# Shield_Proto.net
KiCad netlist of a schematic drawn in EAGLE
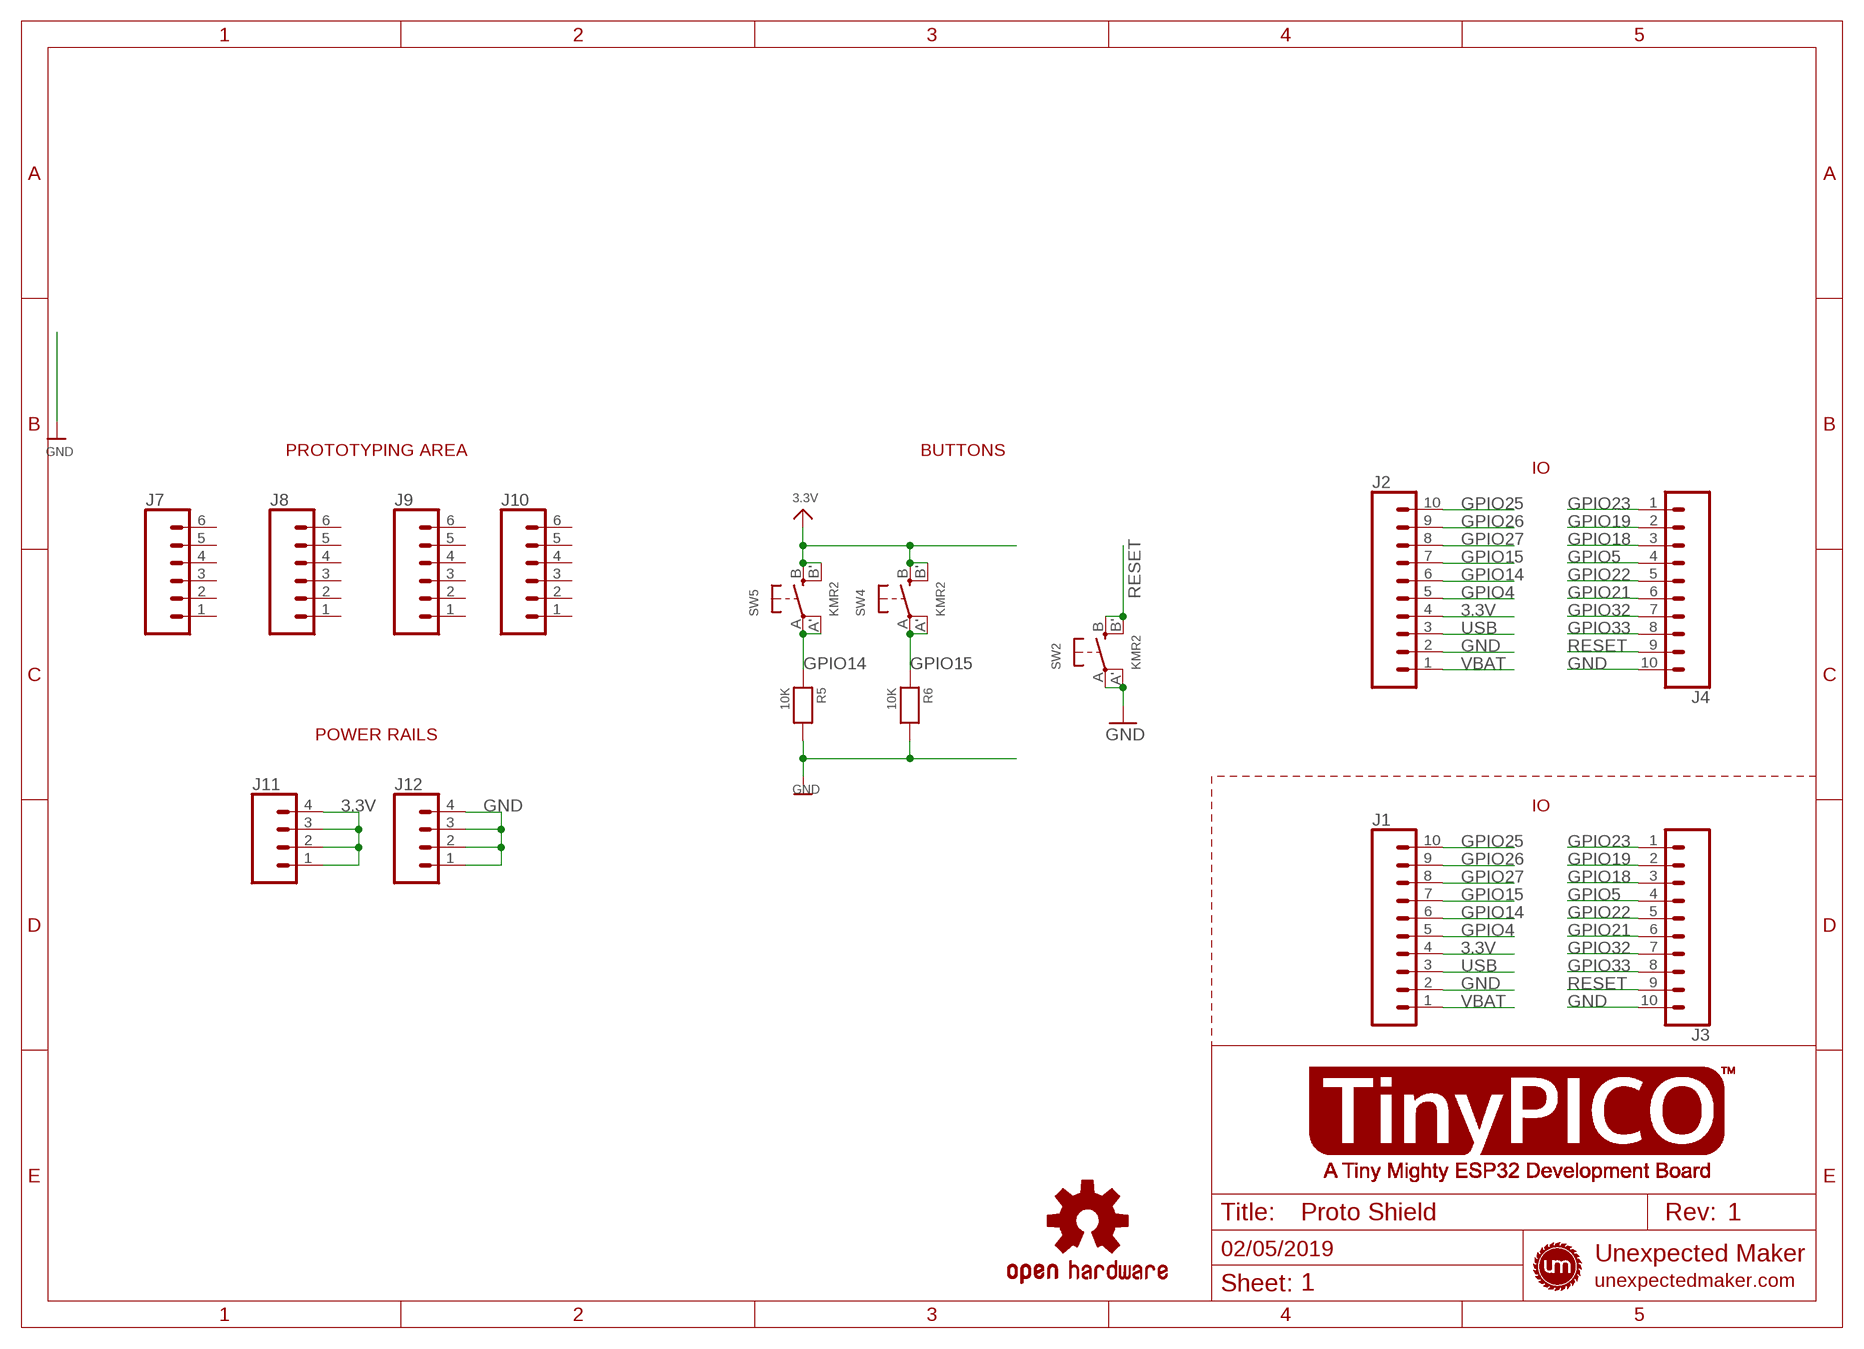
[diagram p0: schematic, sheet 1]

(export (version "E")
  (design (tool "Eeschema 10.0.6"))
  (components
    (comp (ref "J1")
      (value "TINYPICO_HEADER_10NO_SILK_PTH_FEMALE")
      (footprint "eagle-import:1X10_NO_SILK")
      (libsource (lib "eagle-import") (part "TINYPICO_HEADER_10NO_SILK_PTH_FEMALE"))
    )
    (comp (ref "J2")
      (value "TINYPICO_HEADER_10NO_SILK_PTH_FEMALE")
      (footprint "eagle-import:1X10_NO_SILK")
      (libsource (lib "eagle-import") (part "TINYPICO_HEADER_10NO_SILK_PTH_FEMALE"))
    )
    (comp (ref "J3")
      (value "TINYPICO_HEADER_10NO_SILK_PTH_FEMALE")
      (footprint "eagle-import:1X10_NO_SILK")
      (libsource (lib "eagle-import") (part "TINYPICO_HEADER_10NO_SILK_PTH_FEMALE"))
    )
    (comp (ref "J4")
      (value "TINYPICO_HEADER_10NO_SILK_PTH_FEMALE")
      (footprint "eagle-import:1X10_NO_SILK")
      (libsource (lib "eagle-import") (part "TINYPICO_HEADER_10NO_SILK_PTH_FEMALE"))
    )
    (comp (ref "J7")
      (value "CONNECTORS_CONN_06NO_SILK_NO_POP")
      (footprint "eagle-import:SPARKFUN-CONNECTORS_1X06_NO_SILK")
      (libsource (lib "eagle-import") (part "CONNECTORS_CONN_06NO_SILK_NO_POP"))
    )
    (comp (ref "J8")
      (value "CONNECTORS_CONN_06NO_SILK_NO_POP")
      (footprint "eagle-import:SPARKFUN-CONNECTORS_1X06_NO_SILK")
      (libsource (lib "eagle-import") (part "CONNECTORS_CONN_06NO_SILK_NO_POP"))
    )
    (comp (ref "J9")
      (value "CONNECTORS_CONN_06NO_SILK_NO_POP")
      (footprint "eagle-import:SPARKFUN-CONNECTORS_1X06_NO_SILK")
      (libsource (lib "eagle-import") (part "CONNECTORS_CONN_06NO_SILK_NO_POP"))
    )
    (comp (ref "J10")
      (value "CONNECTORS_CONN_06NO_SILK_NO_POP")
      (footprint "eagle-import:SPARKFUN-CONNECTORS_1X06_NO_SILK")
      (libsource (lib "eagle-import") (part "CONNECTORS_CONN_06NO_SILK_NO_POP"))
    )
    (comp (ref "J11")
      (value "CONN_041X04_NO_SILK")
      (footprint "eagle-import:1X04_NO_SILK")
      (libsource (lib "eagle-import") (part "CONN_041X04_NO_SILK"))
    )
    (comp (ref "J12")
      (value "CONN_041X04_NO_SILK")
      (footprint "eagle-import:1X04_NO_SILK")
      (libsource (lib "eagle-import") (part "CONN_041X04_NO_SILK"))
    )
    (comp (ref "LOGO1")
      (value "OSHW-LOGOS")
      (footprint "eagle-import:OSHW-LOGO-S")
      (libsource (lib "eagle-import") (part "OSHW-LOGOS"))
    )
    (comp (ref "R5")
      (value "10K")
      (footprint "eagle-import:_0603MP")
      (libsource (lib "eagle-import") (part "RESISTOR_0603MP"))
    )
    (comp (ref "R6")
      (value "10K")
      (footprint "eagle-import:_0603MP")
      (libsource (lib "eagle-import") (part "RESISTOR_0603MP"))
    )
    (comp (ref "SW2")
      (value "KMR2")
      (footprint "eagle-import:BTN_KMR2_4.6X2.8")
      (libsource (lib "eagle-import") (part "SWITCH_TACT_SMT4.6X2.8"))
    )
    (comp (ref "SW4")
      (value "KMR2")
      (footprint "eagle-import:BTN_KMR2_4.6X2.8")
      (libsource (lib "eagle-import") (part "SWITCH_TACT_SMT4.6X2.8"))
    )
    (comp (ref "SW5")
      (value "KMR2")
      (footprint "eagle-import:BTN_KMR2_4.6X2.8")
      (libsource (lib "eagle-import") (part "SWITCH_TACT_SMT4.6X2.8"))
    )
  )
  (nets
    (net (code "1") (name "/GPIO4") (class "Default")
      (node (ref "J1") (pin "5") (pinfunction "5_5") (pintype "passive"))
      (node (ref "J2") (pin "5") (pinfunction "5_5") (pintype "passive"))
    )
    (net (code "2") (name "/GPIO5") (class "Default")
      (node (ref "J3") (pin "4") (pinfunction "4_4") (pintype "passive"))
      (node (ref "J4") (pin "4") (pinfunction "4_4") (pintype "passive"))
    )
    (net (code "3") (name "/GPIO14") (class "Default")
      (node (ref "J1") (pin "6") (pinfunction "6_6") (pintype "passive"))
      (node (ref "J2") (pin "6") (pinfunction "6_6") (pintype "passive"))
      (node (ref "R5") (pin "1") (pinfunction "1_1") (pintype "passive"))
      (node (ref "SW5") (pin "A") (pinfunction "P_A") (pintype "passive"))
      (node (ref "SW5") (pin "A'") (pinfunction "P1_A'") (pintype "passive"))
    )
    (net (code "4") (name "/GPIO15") (class "Default")
      (node (ref "J1") (pin "7") (pinfunction "7_7") (pintype "passive"))
      (node (ref "J2") (pin "7") (pinfunction "7_7") (pintype "passive"))
      (node (ref "R6") (pin "1") (pinfunction "1_1") (pintype "passive"))
      (node (ref "SW4") (pin "A") (pinfunction "P_A") (pintype "passive"))
      (node (ref "SW4") (pin "A'") (pinfunction "P1_A'") (pintype "passive"))
    )
    (net (code "5") (name "/GPIO18") (class "Default")
      (node (ref "J3") (pin "3") (pinfunction "3_3") (pintype "passive"))
      (node (ref "J4") (pin "3") (pinfunction "3_3") (pintype "passive"))
    )
    (net (code "6") (name "/GPIO19") (class "Default")
      (node (ref "J3") (pin "2") (pinfunction "2_2") (pintype "passive"))
      (node (ref "J4") (pin "2") (pinfunction "2_2") (pintype "passive"))
    )
    (net (code "7") (name "/GPIO21") (class "Default")
      (node (ref "J3") (pin "6") (pinfunction "6_6") (pintype "passive"))
      (node (ref "J4") (pin "6") (pinfunction "6_6") (pintype "passive"))
    )
    (net (code "8") (name "/GPIO22") (class "Default")
      (node (ref "J3") (pin "5") (pinfunction "5_5") (pintype "passive"))
      (node (ref "J4") (pin "5") (pinfunction "5_5") (pintype "passive"))
    )
    (net (code "9") (name "/GPIO23") (class "Default")
      (node (ref "J3") (pin "1") (pinfunction "1_1") (pintype "passive"))
      (node (ref "J4") (pin "1") (pinfunction "1_1") (pintype "passive"))
    )
    (net (code "10") (name "/GPIO25") (class "Default")
      (node (ref "J1") (pin "10") (pinfunction "10_10") (pintype "passive"))
      (node (ref "J2") (pin "10") (pinfunction "10_10") (pintype "passive"))
    )
    (net (code "11") (name "/GPIO26") (class "Default")
      (node (ref "J1") (pin "9") (pinfunction "9_9") (pintype "passive"))
      (node (ref "J2") (pin "9") (pinfunction "9_9") (pintype "passive"))
    )
    (net (code "12") (name "/GPIO27") (class "Default")
      (node (ref "J1") (pin "8") (pinfunction "8_8") (pintype "passive"))
      (node (ref "J2") (pin "8") (pinfunction "8_8") (pintype "passive"))
    )
    (net (code "13") (name "/GPIO32") (class "Default")
      (node (ref "J3") (pin "7") (pinfunction "7_7") (pintype "passive"))
      (node (ref "J4") (pin "7") (pinfunction "7_7") (pintype "passive"))
    )
    (net (code "14") (name "/GPIO33") (class "Default")
      (node (ref "J3") (pin "8") (pinfunction "8_8") (pintype "passive"))
      (node (ref "J4") (pin "8") (pinfunction "8_8") (pintype "passive"))
    )
    (net (code "15") (name "/RESET") (class "Default")
      (node (ref "J3") (pin "9") (pinfunction "9_9") (pintype "passive"))
      (node (ref "J4") (pin "9") (pinfunction "9_9") (pintype "passive"))
      (node (ref "SW2") (pin "B") (pinfunction "S_B") (pintype "passive"))
      (node (ref "SW2") (pin "B'") (pinfunction "S1_B'") (pintype "passive"))
    )
    (net (code "16") (name "/USB") (class "Default")
      (node (ref "J1") (pin "3") (pinfunction "3_3") (pintype "passive"))
      (node (ref "J2") (pin "3") (pinfunction "3_3") (pintype "passive"))
    )
    (net (code "17") (name "/VBAT") (class "Default")
      (node (ref "J1") (pin "1") (pinfunction "1_1") (pintype "passive"))
      (node (ref "J2") (pin "1") (pinfunction "1_1") (pintype "passive"))
    )
    (net (code "18") (name "3.3V") (class "Default")
      (node (ref "J1") (pin "4") (pinfunction "4_4") (pintype "passive"))
      (node (ref "J11") (pin "1") (pinfunction "1_1") (pintype "passive"))
      (node (ref "J11") (pin "2") (pinfunction "2_2") (pintype "passive"))
      (node (ref "J11") (pin "3") (pinfunction "3_3") (pintype "passive"))
      (node (ref "J11") (pin "4") (pinfunction "4_4") (pintype "passive"))
      (node (ref "J2") (pin "4") (pinfunction "4_4") (pintype "passive"))
      (node (ref "SW4") (pin "B") (pinfunction "S_B") (pintype "passive"))
      (node (ref "SW4") (pin "B'") (pinfunction "S1_B'") (pintype "passive"))
      (node (ref "SW5") (pin "B") (pinfunction "S_B") (pintype "passive"))
      (node (ref "SW5") (pin "B'") (pinfunction "S1_B'") (pintype "passive"))
    )
    (net (code "19") (name "GND") (class "Default")
      (node (ref "J1") (pin "2") (pinfunction "2_2") (pintype "passive"))
      (node (ref "J12") (pin "1") (pinfunction "1_1") (pintype "passive"))
      (node (ref "J12") (pin "2") (pinfunction "2_2") (pintype "passive"))
      (node (ref "J12") (pin "3") (pinfunction "3_3") (pintype "passive"))
      (node (ref "J12") (pin "4") (pinfunction "4_4") (pintype "passive"))
      (node (ref "J2") (pin "2") (pinfunction "2_2") (pintype "passive"))
      (node (ref "J3") (pin "10") (pinfunction "10_10") (pintype "passive"))
      (node (ref "J4") (pin "10") (pinfunction "10_10") (pintype "passive"))
      (node (ref "R5") (pin "2") (pinfunction "2_2") (pintype "passive"))
      (node (ref "R6") (pin "2") (pinfunction "2_2") (pintype "passive"))
      (node (ref "SW2") (pin "A") (pinfunction "P_A") (pintype "passive"))
      (node (ref "SW2") (pin "A'") (pinfunction "P1_A'") (pintype "passive"))
    )
    (net (code "20") (name "unconnected-(J7-Pad1)") (class "Default")
      (node (ref "J7") (pin "1") (pinfunction "1_1") (pintype "passive"))
    )
    (net (code "21") (name "unconnected-(J7-Pad2)") (class "Default")
      (node (ref "J7") (pin "2") (pinfunction "2_2") (pintype "passive"))
    )
    (net (code "22") (name "unconnected-(J7-Pad3)") (class "Default")
      (node (ref "J7") (pin "3") (pinfunction "3_3") (pintype "passive"))
    )
    (net (code "23") (name "unconnected-(J7-Pad4)") (class "Default")
      (node (ref "J7") (pin "4") (pinfunction "4_4") (pintype "passive"))
    )
    (net (code "24") (name "unconnected-(J7-Pad5)") (class "Default")
      (node (ref "J7") (pin "5") (pinfunction "5_5") (pintype "passive"))
    )
    (net (code "25") (name "unconnected-(J7-Pad6)") (class "Default")
      (node (ref "J7") (pin "6") (pinfunction "6_6") (pintype "passive"))
    )
    (net (code "26") (name "unconnected-(J8-Pad1)") (class "Default")
      (node (ref "J8") (pin "1") (pinfunction "1_1") (pintype "passive"))
    )
    (net (code "27") (name "unconnected-(J8-Pad2)") (class "Default")
      (node (ref "J8") (pin "2") (pinfunction "2_2") (pintype "passive"))
    )
    (net (code "28") (name "unconnected-(J8-Pad3)") (class "Default")
      (node (ref "J8") (pin "3") (pinfunction "3_3") (pintype "passive"))
    )
    (net (code "29") (name "unconnected-(J8-Pad4)") (class "Default")
      (node (ref "J8") (pin "4") (pinfunction "4_4") (pintype "passive"))
    )
    (net (code "30") (name "unconnected-(J8-Pad5)") (class "Default")
      (node (ref "J8") (pin "5") (pinfunction "5_5") (pintype "passive"))
    )
    (net (code "31") (name "unconnected-(J8-Pad6)") (class "Default")
      (node (ref "J8") (pin "6") (pinfunction "6_6") (pintype "passive"))
    )
    (net (code "32") (name "unconnected-(J9-Pad1)") (class "Default")
      (node (ref "J9") (pin "1") (pinfunction "1_1") (pintype "passive"))
    )
    (net (code "33") (name "unconnected-(J9-Pad2)") (class "Default")
      (node (ref "J9") (pin "2") (pinfunction "2_2") (pintype "passive"))
    )
    (net (code "34") (name "unconnected-(J9-Pad3)") (class "Default")
      (node (ref "J9") (pin "3") (pinfunction "3_3") (pintype "passive"))
    )
    (net (code "35") (name "unconnected-(J9-Pad4)") (class "Default")
      (node (ref "J9") (pin "4") (pinfunction "4_4") (pintype "passive"))
    )
    (net (code "36") (name "unconnected-(J9-Pad5)") (class "Default")
      (node (ref "J9") (pin "5") (pinfunction "5_5") (pintype "passive"))
    )
    (net (code "37") (name "unconnected-(J9-Pad6)") (class "Default")
      (node (ref "J9") (pin "6") (pinfunction "6_6") (pintype "passive"))
    )
    (net (code "38") (name "unconnected-(J10-Pad1)") (class "Default")
      (node (ref "J10") (pin "1") (pinfunction "1_1") (pintype "passive"))
    )
    (net (code "39") (name "unconnected-(J10-Pad2)") (class "Default")
      (node (ref "J10") (pin "2") (pinfunction "2_2") (pintype "passive"))
    )
    (net (code "40") (name "unconnected-(J10-Pad3)") (class "Default")
      (node (ref "J10") (pin "3") (pinfunction "3_3") (pintype "passive"))
    )
    (net (code "41") (name "unconnected-(J10-Pad4)") (class "Default")
      (node (ref "J10") (pin "4") (pinfunction "4_4") (pintype "passive"))
    )
    (net (code "42") (name "unconnected-(J10-Pad5)") (class "Default")
      (node (ref "J10") (pin "5") (pinfunction "5_5") (pintype "passive"))
    )
    (net (code "43") (name "unconnected-(J10-Pad6)") (class "Default")
      (node (ref "J10") (pin "6") (pinfunction "6_6") (pintype "passive"))
    )
  )
)
